# SNS_INPUT.net
KiCad netlist of a schematic drawn in Altium Designer
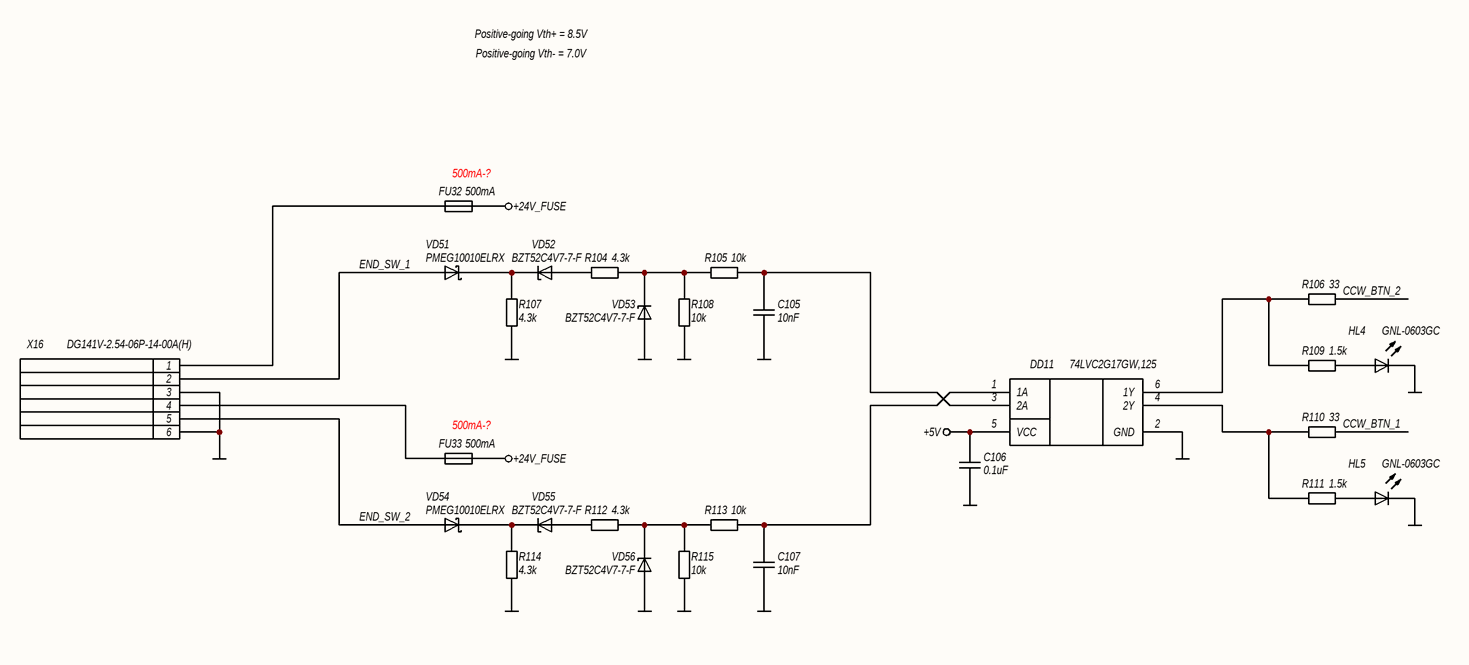
[diagram p0: SNS_INPUT.SchDoc]

(export (version "E")
  (design (tool "Eeschema 10.0.6"))
  (components
    (comp (ref "C105")
      (value "10nF")
      (footprint "C0603N")
      (description "Конденсатор")
      (libsource (lib "Components Library") (part "CAP_FIXED"))
    )
    (comp (ref "C106")
      (value "0.1uF")
      (footprint "C0603N")
      (description "Конденсатор")
      (libsource (lib "Components Library") (part "CAP_FIXED"))
    )
    (comp (ref "C107")
      (value "10nF")
      (footprint "C0603N")
      (description "Конденсатор")
      (libsource (lib "Components Library") (part "CAP_FIXED"))
    )
    (comp (ref "DD11")
      (value "74LVC2G17GW,125")
      (footprint "SOT363-2")
      (description "Микросхема сдвоенный триггер Шмитта")
      (libsource (lib "Components Library") (part "74LVC2G17"))
    )
    (comp (ref "FU32")
      (value "500mA")
      (footprint "MF-MSMF")
      (description "Плавкий предохранитель")
      (libsource (lib "Components Library") (part "FUSE"))
    )
    (comp (ref "FU33")
      (value "500mA")
      (footprint "MF-MSMF")
      (description "Плавкий предохранитель")
      (libsource (lib "Components Library") (part "FUSE"))
    )
    (comp (ref "HL4")
      (value "GNL-0603GC")
      (footprint "LED0603")
      (description "Светодиод")
      (libsource (lib "Components Library") (part "LED"))
    )
    (comp (ref "HL5")
      (value "GNL-0603GC")
      (footprint "LED0603")
      (description "Светодиод")
      (libsource (lib "Components Library") (part "LED"))
    )
    (comp (ref "R104")
      (value "4.3k")
      (footprint "R1206N")
      (description "Резистор")
      (libsource (lib "") (part "RES_FIXED_1"))
    )
    (comp (ref "R105")
      (value "10k")
      (footprint "R0603N")
      (description "Резистор")
      (libsource (lib "") (part "RES_FIXED_1"))
    )
    (comp (ref "R106")
      (value "33")
      (footprint "R0603N")
      (description "Резистор")
      (libsource (lib "Components Library") (part "RES_FIXED"))
    )
    (comp (ref "R107")
      (value "4.3k")
      (footprint "R1206N")
      (description "Резистор")
      (libsource (lib "Components Library") (part "RES_FIXED"))
    )
    (comp (ref "R108")
      (value "10k")
      (footprint "R0603N")
      (description "Резистор")
      (libsource (lib "Components Library") (part "RES_FIXED"))
    )
    (comp (ref "R109")
      (value "1.5k")
      (footprint "R0603N")
      (description "Резистор")
      (libsource (lib "Components Library") (part "RES_FIXED"))
    )
    (comp (ref "R110")
      (value "33")
      (footprint "R0603N")
      (description "Резистор")
      (libsource (lib "Components Library") (part "RES_FIXED"))
    )
    (comp (ref "R111")
      (value "1.5k")
      (footprint "R0603N")
      (description "Резистор")
      (libsource (lib "Components Library") (part "RES_FIXED"))
    )
    (comp (ref "R112")
      (value "4.3k")
      (footprint "R1206N")
      (description "Резистор")
      (libsource (lib "") (part "RES_FIXED_1"))
    )
    (comp (ref "R113")
      (value "10k")
      (footprint "R0603N")
      (description "Резистор")
      (libsource (lib "") (part "RES_FIXED_1"))
    )
    (comp (ref "R114")
      (value "4.3k")
      (footprint "R1206N")
      (description "Резистор")
      (libsource (lib "Components Library") (part "RES_FIXED"))
    )
    (comp (ref "R115")
      (value "10k")
      (footprint "R0603N")
      (description "Резистор")
      (libsource (lib "Components Library") (part "RES_FIXED"))
    )
    (comp (ref "VD51")
      (value "PMEG10010ELRX")
      (footprint "SOD123W")
      (description "Диод Шоттки")
      (libsource (lib "Components Library") (part "SCHOTTKY"))
    )
    (comp (ref "VD52")
      (value "BZT52C4V7-7-F")
      (footprint "SOD123")
      (description "Стабилитрон")
      (libsource (lib "Components Library") (part "ZENER"))
    )
    (comp (ref "VD53")
      (value "BZT52C4V7-7-F")
      (footprint "SOD123")
      (description "Стабилитрон")
      (libsource (lib "Components Library") (part "ZENER"))
    )
    (comp (ref "VD54")
      (value "PMEG10010ELRX")
      (footprint "SOD123W")
      (description "Диод Шоттки")
      (libsource (lib "Components Library") (part "SCHOTTKY"))
    )
    (comp (ref "VD55")
      (value "BZT52C4V7-7-F")
      (footprint "SOD123")
      (description "Стабилитрон")
      (libsource (lib "Components Library") (part "ZENER"))
    )
    (comp (ref "VD56")
      (value "BZT52C4V7-7-F")
      (footprint "SOD123")
      (description "Стабилитрон")
      (libsource (lib "Components Library") (part "ZENER"))
    )
    (comp (ref "X16")
      (value "DG141V-2.54-06P-14-00A(H)")
      (footprint "DG141V-2.54-06P-14-00A(H)")
      (description "Разъем, 6 контактов")
      (libsource (lib "Components Library") (part "Connector 6"))
    )
  )
  (nets
    (net (code "1") (name "+5V") (class "Default")
      (node (ref "C106") (pin "2") (pinfunction "2_2") (pintype "passive"))
      (node (ref "DD11") (pin "5") (pinfunction "VCC_5") (pintype "power_in"))
    )
    (net (code "2") (name "+24V_FUSE") (class "Default")
      (node (ref "FU32") (pin "2") (pinfunction "2_2") (pintype "passive"))
      (node (ref "FU33") (pin "2") (pinfunction "2_2") (pintype "passive"))
    )
    (net (code "3") (name "/CCW_BTN_1") (class "Default")
      (node (ref "R110") (pin "1") (pinfunction "1_1") (pintype "passive"))
    )
    (net (code "4") (name "/CCW_BTN_2") (class "Default")
      (node (ref "R106") (pin "1") (pinfunction "1_1") (pintype "passive"))
    )
    (net (code "5") (name "/END_SW_1") (class "Default")
      (node (ref "VD51") (pin "2") (pinfunction "A_2") (pintype "passive"))
      (node (ref "X16") (pin "2") (pinfunction "2_2") (pintype "power_in"))
    )
    (net (code "6") (name "/END_SW_2") (class "Default")
      (node (ref "VD54") (pin "2") (pinfunction "A_2") (pintype "passive"))
      (node (ref "X16") (pin "5") (pinfunction "5_5") (pintype "power_in"))
    )
    (net (code "7") (name "GND") (class "Default")
      (node (ref "C105") (pin "2") (pinfunction "2_2") (pintype "passive"))
      (node (ref "C106") (pin "1") (pinfunction "1_1") (pintype "passive"))
      (node (ref "C107") (pin "2") (pinfunction "2_2") (pintype "passive"))
      (node (ref "DD11") (pin "2") (pinfunction "GND_2") (pintype "power_in"))
      (node (ref "HL4") (pin "1") (pinfunction "K_1") (pintype "passive"))
      (node (ref "HL5") (pin "1") (pinfunction "K_1") (pintype "passive"))
      (node (ref "R107") (pin "2") (pinfunction "2_2") (pintype "passive"))
      (node (ref "R108") (pin "2") (pinfunction "2_2") (pintype "passive"))
      (node (ref "R114") (pin "2") (pinfunction "2_2") (pintype "passive"))
      (node (ref "R115") (pin "2") (pinfunction "2_2") (pintype "passive"))
      (node (ref "VD53") (pin "2") (pinfunction "A_2") (pintype "passive"))
      (node (ref "VD56") (pin "2") (pinfunction "A_2") (pintype "passive"))
      (node (ref "X16") (pin "3") (pinfunction "3_3") (pintype "power_in"))
      (node (ref "X16") (pin "6") (pinfunction "6_6") (pintype "power_in"))
    )
    (net (code "8") (name "Net-(DD11-1A)") (class "Default")
      (node (ref "C107") (pin "1") (pinfunction "1_1") (pintype "passive"))
      (node (ref "DD11") (pin "1") (pinfunction "1A_1") (pintype "power_in"))
      (node (ref "R113") (pin "1") (pinfunction "1_1") (pintype "passive"))
    )
    (net (code "9") (name "Net-(DD11-1Y)") (class "Default")
      (node (ref "DD11") (pin "6") (pinfunction "1Y_6") (pintype "power_in"))
      (node (ref "R106") (pin "2") (pinfunction "2_2") (pintype "passive"))
      (node (ref "R109") (pin "2") (pinfunction "2_2") (pintype "passive"))
    )
    (net (code "10") (name "Net-(DD11-2A)") (class "Default")
      (node (ref "C105") (pin "1") (pinfunction "1_1") (pintype "passive"))
      (node (ref "DD11") (pin "3") (pinfunction "2A_3") (pintype "power_in"))
      (node (ref "R105") (pin "1") (pinfunction "1_1") (pintype "passive"))
    )
    (net (code "11") (name "Net-(DD11-2Y)") (class "Default")
      (node (ref "DD11") (pin "4") (pinfunction "2Y_4") (pintype "power_in"))
      (node (ref "R110") (pin "2") (pinfunction "2_2") (pintype "passive"))
      (node (ref "R111") (pin "2") (pinfunction "2_2") (pintype "passive"))
    )
    (net (code "12") (name "Net-(FU32-Pad1)") (class "Default")
      (node (ref "FU32") (pin "1") (pinfunction "1_1") (pintype "passive"))
      (node (ref "X16") (pin "1") (pinfunction "1_1") (pintype "power_in"))
    )
    (net (code "13") (name "Net-(FU33-Pad1)") (class "Default")
      (node (ref "FU33") (pin "1") (pinfunction "1_1") (pintype "passive"))
      (node (ref "X16") (pin "4") (pinfunction "4_4") (pintype "power_in"))
    )
    (net (code "14") (name "Net-(HL4-A)") (class "Default")
      (node (ref "HL4") (pin "2") (pinfunction "A_2") (pintype "passive"))
      (node (ref "R109") (pin "1") (pinfunction "1_1") (pintype "passive"))
    )
    (net (code "15") (name "Net-(HL5-A)") (class "Default")
      (node (ref "HL5") (pin "2") (pinfunction "A_2") (pintype "passive"))
      (node (ref "R111") (pin "1") (pinfunction "1_1") (pintype "passive"))
    )
    (net (code "16") (name "Net-(VD51-K)") (class "Default")
      (node (ref "R107") (pin "1") (pinfunction "1_1") (pintype "passive"))
      (node (ref "VD51") (pin "1") (pinfunction "K_1") (pintype "passive"))
      (node (ref "VD52") (pin "1") (pinfunction "K_1") (pintype "passive"))
    )
    (net (code "17") (name "Net-(VD52-A)") (class "Default")
      (node (ref "R104") (pin "2") (pinfunction "2_2") (pintype "passive"))
      (node (ref "VD52") (pin "2") (pinfunction "A_2") (pintype "passive"))
    )
    (net (code "18") (name "Net-(VD53-K)") (class "Default")
      (node (ref "R104") (pin "1") (pinfunction "1_1") (pintype "passive"))
      (node (ref "R105") (pin "2") (pinfunction "2_2") (pintype "passive"))
      (node (ref "R108") (pin "1") (pinfunction "1_1") (pintype "passive"))
      (node (ref "VD53") (pin "1") (pinfunction "K_1") (pintype "passive"))
    )
    (net (code "19") (name "Net-(VD54-K)") (class "Default")
      (node (ref "R114") (pin "1") (pinfunction "1_1") (pintype "passive"))
      (node (ref "VD54") (pin "1") (pinfunction "K_1") (pintype "passive"))
      (node (ref "VD55") (pin "1") (pinfunction "K_1") (pintype "passive"))
    )
    (net (code "20") (name "Net-(VD55-A)") (class "Default")
      (node (ref "R112") (pin "2") (pinfunction "2_2") (pintype "passive"))
      (node (ref "VD55") (pin "2") (pinfunction "A_2") (pintype "passive"))
    )
    (net (code "21") (name "Net-(VD56-K)") (class "Default")
      (node (ref "R112") (pin "1") (pinfunction "1_1") (pintype "passive"))
      (node (ref "R113") (pin "2") (pinfunction "2_2") (pintype "passive"))
      (node (ref "R115") (pin "1") (pinfunction "1_1") (pintype "passive"))
      (node (ref "VD56") (pin "1") (pinfunction "K_1") (pintype "passive"))
    )
  )
)
